# Display_Schematic.net
KiCad netlist of a schematic drawn in Altium Designer
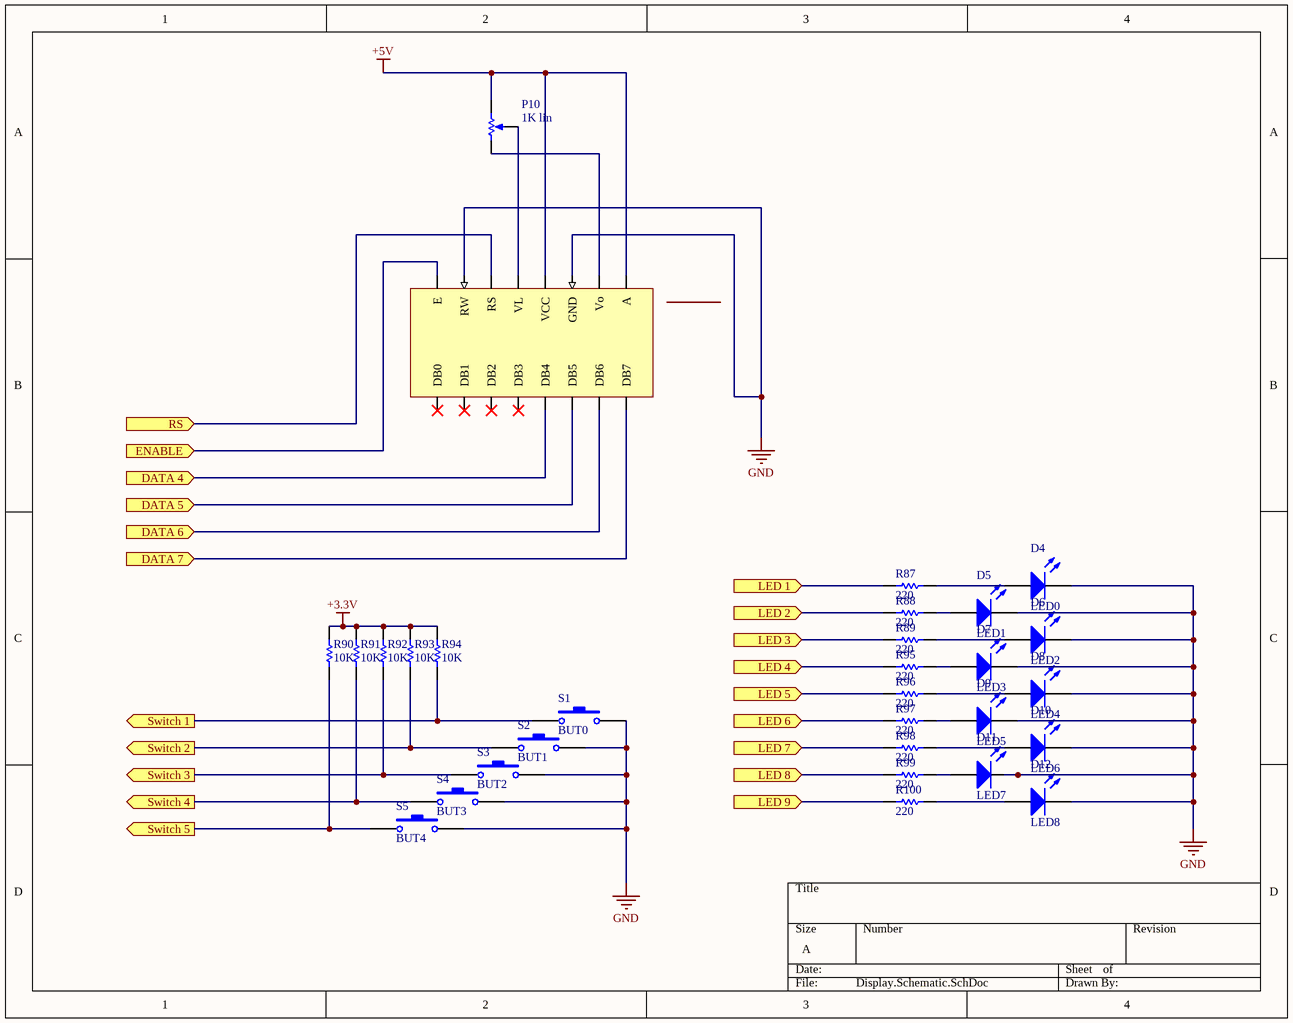
[diagram p0: Display.Schematic.SchDoc]

(export (version "E")
  (design (tool "Eeschema 10.0.6"))
  (components
    (comp (ref "D4")
      (value "LED0")
      (footprint "LED")
      (description "Typical INFRARED GaAs LED")
      (fields (field (name "PUBLISHER") "Altium Limited"))
      (libsource (lib "Miscellaneous Devices") (part "LED0"))
    )
    (comp (ref "D5")
      (value "LED1")
      (footprint "LED")
      (description "Typical INFRARED GaAs LED")
      (fields (field (name "PUBLISHER") "Altium Limited"))
      (libsource (lib "Miscellaneous Devices") (part "LED0"))
    )
    (comp (ref "D6")
      (value "LED2")
      (footprint "LED")
      (description "Typical INFRARED GaAs LED")
      (fields (field (name "PUBLISHER") "Altium Limited"))
      (libsource (lib "Miscellaneous Devices") (part "LED0"))
    )
    (comp (ref "D7")
      (value "LED3")
      (footprint "LED")
      (description "Typical INFRARED GaAs LED")
      (fields (field (name "PUBLISHER") "Altium Limited"))
      (libsource (lib "Miscellaneous Devices") (part "LED0"))
    )
    (comp (ref "D8")
      (value "LED4")
      (footprint "LED")
      (description "Typical INFRARED GaAs LED")
      (fields (field (name "PUBLISHER") "Altium Limited"))
      (libsource (lib "Miscellaneous Devices") (part "LED0"))
    )
    (comp (ref "D9")
      (value "LED5")
      (footprint "LED")
      (description "Typical INFRARED GaAs LED")
      (fields (field (name "PUBLISHER") "Altium Limited"))
      (libsource (lib "Miscellaneous Devices") (part "LED0"))
    )
    (comp (ref "D10")
      (value "LED6")
      (footprint "LED")
      (description "Typical INFRARED GaAs LED")
      (fields (field (name "PUBLISHER") "Altium Limited"))
      (libsource (lib "Miscellaneous Devices") (part "LED0"))
    )
    (comp (ref "D11")
      (value "LED7")
      (footprint "LED")
      (description "Typical INFRARED GaAs LED")
      (fields (field (name "PUBLISHER") "Altium Limited"))
      (libsource (lib "Miscellaneous Devices") (part "LED0"))
    )
    (comp (ref "D12")
      (value "LED8")
      (footprint "LED")
      (description "Typical INFRARED GaAs LED")
      (fields (field (name "PUBLISHER") "Altium Limited"))
      (libsource (lib "Miscellaneous Devices") (part "LED0"))
    )
    (comp (ref "Display1")
      (value "16x2 LCD")
      (footprint "Display")
      (libsource (lib "display") (part "Display"))
    )
    (comp (ref "P10")
      (value "1K lin")
      (footprint "BOURNS Trim pot")
      (description "Potentiometer")
      (fields (field (name "PUBLISHER") "Altium Limited"))
      (libsource (lib "Miscellaneous Devices") (part "RPot"))
    )
    (comp (ref "R87")
      (value "220")
      (footprint "CAPC1608N")
      (description "Resistor")
      (fields (field (name "PUBLISHER") "Altium Limited"))
      (libsource (lib "Miscellaneous Devices") (part "Res1"))
    )
    (comp (ref "R88")
      (value "220")
      (footprint "CAPC1608N")
      (description "Resistor")
      (fields (field (name "PUBLISHER") "Altium Limited"))
      (libsource (lib "Miscellaneous Devices") (part "Res1"))
    )
    (comp (ref "R89")
      (value "220")
      (footprint "CAPC1608N")
      (description "Resistor")
      (fields (field (name "PUBLISHER") "Altium Limited"))
      (libsource (lib "Miscellaneous Devices") (part "Res1"))
    )
    (comp (ref "R90")
      (value "10K")
      (footprint "CAPC1608N")
      (description "Resistor")
      (fields (field (name "PUBLISHER") "Altium Limited"))
      (libsource (lib "Miscellaneous Devices") (part "Res1"))
    )
    (comp (ref "R91")
      (value "10K")
      (footprint "CAPC1608N")
      (description "Resistor")
      (fields (field (name "PUBLISHER") "Altium Limited"))
      (libsource (lib "Miscellaneous Devices") (part "Res1"))
    )
    (comp (ref "R92")
      (value "10K")
      (footprint "CAPC1608N")
      (description "Resistor")
      (fields (field (name "PUBLISHER") "Altium Limited"))
      (libsource (lib "Miscellaneous Devices") (part "Res1"))
    )
    (comp (ref "R93")
      (value "10K")
      (footprint "CAPC1608N")
      (description "Resistor")
      (fields (field (name "PUBLISHER") "Altium Limited"))
      (libsource (lib "Miscellaneous Devices") (part "Res1"))
    )
    (comp (ref "R94")
      (value "10K")
      (footprint "CAPC1608N")
      (description "Resistor")
      (fields (field (name "PUBLISHER") "Altium Limited"))
      (libsource (lib "Miscellaneous Devices") (part "Res1"))
    )
    (comp (ref "R95")
      (value "220")
      (footprint "CAPC1608N")
      (description "Resistor")
      (fields (field (name "PUBLISHER") "Altium Limited"))
      (libsource (lib "Miscellaneous Devices") (part "Res1"))
    )
    (comp (ref "R96")
      (value "220")
      (footprint "CAPC1608N")
      (description "Resistor")
      (fields (field (name "PUBLISHER") "Altium Limited"))
      (libsource (lib "Miscellaneous Devices") (part "Res1"))
    )
    (comp (ref "R97")
      (value "220")
      (footprint "CAPC1608N")
      (description "Resistor")
      (fields (field (name "PUBLISHER") "Altium Limited"))
      (libsource (lib "Miscellaneous Devices") (part "Res1"))
    )
    (comp (ref "R98")
      (value "220")
      (footprint "CAPC1608N")
      (description "Resistor")
      (fields (field (name "PUBLISHER") "Altium Limited"))
      (libsource (lib "Miscellaneous Devices") (part "Res1"))
    )
    (comp (ref "R99")
      (value "220")
      (footprint "CAPC1608N")
      (description "Resistor")
      (fields (field (name "PUBLISHER") "Altium Limited"))
      (libsource (lib "Miscellaneous Devices") (part "Res1"))
    )
    (comp (ref "R100")
      (value "220")
      (footprint "CAPC1608N")
      (description "Resistor")
      (fields (field (name "PUBLISHER") "Altium Limited"))
      (libsource (lib "Miscellaneous Devices") (part "Res1"))
    )
    (comp (ref "S1")
      (value "BUT0")
      (footprint "PUSH BUTTON")
      (description "Switch")
      (fields (field (name "PUBLISHER") "Altium Limited"))
      (libsource (lib "Miscellaneous Devices") (part "SW-PB"))
    )
    (comp (ref "S2")
      (value "BUT1")
      (footprint "PUSH BUTTON")
      (description "Switch")
      (fields (field (name "PUBLISHER") "Altium Limited"))
      (libsource (lib "Miscellaneous Devices") (part "SW-PB"))
    )
    (comp (ref "S3")
      (value "BUT2")
      (footprint "PUSH BUTTON")
      (description "Switch")
      (fields (field (name "PUBLISHER") "Altium Limited"))
      (libsource (lib "Miscellaneous Devices") (part "SW-PB"))
    )
    (comp (ref "S4")
      (value "BUT3")
      (footprint "PUSH BUTTON")
      (description "Switch")
      (fields (field (name "PUBLISHER") "Altium Limited"))
      (libsource (lib "Miscellaneous Devices") (part "SW-PB"))
    )
    (comp (ref "S5")
      (value "BUT4")
      (footprint "PUSH BUTTON")
      (description "Switch")
      (fields (field (name "PUBLISHER") "Altium Limited"))
      (libsource (lib "Miscellaneous Devices") (part "SW-PB"))
    )
  )
  (nets
    (net (code "1") (name "+3.3V") (class "Default")
      (node (ref "R90") (pin "2") (pinfunction "2_2") (pintype "passive"))
      (node (ref "R91") (pin "2") (pinfunction "2_2") (pintype "passive"))
      (node (ref "R92") (pin "2") (pinfunction "2_2") (pintype "passive"))
      (node (ref "R93") (pin "2") (pinfunction "2_2") (pintype "passive"))
      (node (ref "R94") (pin "2") (pinfunction "2_2") (pintype "passive"))
    )
    (net (code "2") (name "+5V") (class "Default")
      (node (ref "Display1") (pin "16") (pinfunction "A_16") (pintype "passive"))
      (node (ref "Display1") (pin "2") (pinfunction "VCC_2") (pintype "passive"))
      (node (ref "P10") (pin "2") (pinfunction "BOT_2") (pintype "passive"))
    )
    (net (code "3") (name "/DATA 4") (class "Default")
      (node (ref "Display1") (pin "10") (pinfunction "DB4_10") (pintype "passive"))
    )
    (net (code "4") (name "/DATA 5") (class "Default")
      (node (ref "Display1") (pin "9") (pinfunction "DB5_9") (pintype "passive"))
    )
    (net (code "5") (name "/DATA 6") (class "Default")
      (node (ref "Display1") (pin "8") (pinfunction "DB6_8") (pintype "passive"))
    )
    (net (code "6") (name "/DATA 7") (class "Default")
      (node (ref "Display1") (pin "7") (pinfunction "DB7_7") (pintype "passive"))
    )
    (net (code "7") (name "/ENABLE") (class "Default")
      (node (ref "Display1") (pin "6") (pinfunction "E_6") (pintype "passive"))
    )
    (net (code "8") (name "/LED 1") (class "Default")
      (node (ref "R87") (pin "1") (pinfunction "1_1") (pintype "passive"))
    )
    (net (code "9") (name "/LED 2") (class "Default")
      (node (ref "R88") (pin "1") (pinfunction "1_1") (pintype "passive"))
    )
    (net (code "10") (name "/LED 3") (class "Default")
      (node (ref "R89") (pin "1") (pinfunction "1_1") (pintype "passive"))
    )
    (net (code "11") (name "/LED 4") (class "Default")
      (node (ref "R95") (pin "1") (pinfunction "1_1") (pintype "passive"))
    )
    (net (code "12") (name "/LED 5") (class "Default")
      (node (ref "R96") (pin "1") (pinfunction "1_1") (pintype "passive"))
    )
    (net (code "13") (name "/LED 6") (class "Default")
      (node (ref "R97") (pin "1") (pinfunction "1_1") (pintype "passive"))
    )
    (net (code "14") (name "/LED 7") (class "Default")
      (node (ref "R98") (pin "1") (pinfunction "1_1") (pintype "passive"))
    )
    (net (code "15") (name "/LED 8") (class "Default")
      (node (ref "R99") (pin "1") (pinfunction "1_1") (pintype "passive"))
    )
    (net (code "16") (name "/LED 9") (class "Default")
      (node (ref "R100") (pin "1") (pinfunction "1_1") (pintype "passive"))
    )
    (net (code "17") (name "/RS") (class "Default")
      (node (ref "Display1") (pin "4") (pinfunction "RS_4") (pintype "passive"))
    )
    (net (code "18") (name "/Switch 1") (class "Default")
      (node (ref "R94") (pin "1") (pinfunction "1_1") (pintype "passive"))
      (node (ref "S1") (pin "1") (pinfunction "1_1") (pintype "passive"))
    )
    (net (code "19") (name "/Switch 2") (class "Default")
      (node (ref "R93") (pin "1") (pinfunction "1_1") (pintype "passive"))
      (node (ref "S2") (pin "1") (pinfunction "1_1") (pintype "passive"))
    )
    (net (code "20") (name "/Switch 3") (class "Default")
      (node (ref "R92") (pin "1") (pinfunction "1_1") (pintype "passive"))
      (node (ref "S3") (pin "1") (pinfunction "1_1") (pintype "passive"))
    )
    (net (code "21") (name "/Switch 4") (class "Default")
      (node (ref "R91") (pin "1") (pinfunction "1_1") (pintype "passive"))
      (node (ref "S4") (pin "1") (pinfunction "1_1") (pintype "passive"))
    )
    (net (code "22") (name "/Switch 5") (class "Default")
      (node (ref "R90") (pin "1") (pinfunction "1_1") (pintype "passive"))
      (node (ref "S5") (pin "1") (pinfunction "1_1") (pintype "passive"))
    )
    (net (code "23") (name "GND") (class "Default")
      (node (ref "D10") (pin "2") (pinfunction "K_2") (pintype "passive"))
      (node (ref "D11") (pin "2") (pinfunction "K_2") (pintype "passive"))
      (node (ref "D12") (pin "2") (pinfunction "K_2") (pintype "passive"))
      (node (ref "D4") (pin "2") (pinfunction "K_2") (pintype "passive"))
      (node (ref "D5") (pin "2") (pinfunction "K_2") (pintype "passive"))
      (node (ref "D6") (pin "2") (pinfunction "K_2") (pintype "passive"))
      (node (ref "D7") (pin "2") (pinfunction "K_2") (pintype "passive"))
      (node (ref "D8") (pin "2") (pinfunction "K_2") (pintype "passive"))
      (node (ref "D9") (pin "2") (pinfunction "K_2") (pintype "passive"))
      (node (ref "Display1") (pin "1") (pinfunction "GND_1") (pintype "input"))
      (node (ref "Display1") (pin "5") (pinfunction "RW_5") (pintype "input"))
      (node (ref "S1") (pin "2") (pinfunction "2_2") (pintype "passive"))
      (node (ref "S2") (pin "2") (pinfunction "2_2") (pintype "passive"))
      (node (ref "S3") (pin "2") (pinfunction "2_2") (pintype "passive"))
      (node (ref "S4") (pin "2") (pinfunction "2_2") (pintype "passive"))
      (node (ref "S5") (pin "2") (pinfunction "2_2") (pintype "passive"))
    )
    (net (code "24") (name "Net-(D4-A)") (class "Default")
      (node (ref "D4") (pin "1") (pinfunction "A_1") (pintype "passive"))
      (node (ref "R87") (pin "2") (pinfunction "2_2") (pintype "passive"))
    )
    (net (code "25") (name "Net-(D5-A)") (class "Default")
      (node (ref "D5") (pin "1") (pinfunction "A_1") (pintype "passive"))
      (node (ref "R88") (pin "2") (pinfunction "2_2") (pintype "passive"))
    )
    (net (code "26") (name "Net-(D6-A)") (class "Default")
      (node (ref "D6") (pin "1") (pinfunction "A_1") (pintype "passive"))
      (node (ref "R89") (pin "2") (pinfunction "2_2") (pintype "passive"))
    )
    (net (code "27") (name "Net-(D7-A)") (class "Default")
      (node (ref "D7") (pin "1") (pinfunction "A_1") (pintype "passive"))
      (node (ref "R95") (pin "2") (pinfunction "2_2") (pintype "passive"))
    )
    (net (code "28") (name "Net-(D8-A)") (class "Default")
      (node (ref "D8") (pin "1") (pinfunction "A_1") (pintype "passive"))
      (node (ref "R96") (pin "2") (pinfunction "2_2") (pintype "passive"))
    )
    (net (code "29") (name "Net-(D9-A)") (class "Default")
      (node (ref "D9") (pin "1") (pinfunction "A_1") (pintype "passive"))
      (node (ref "R97") (pin "2") (pinfunction "2_2") (pintype "passive"))
    )
    (net (code "30") (name "Net-(D10-A)") (class "Default")
      (node (ref "D10") (pin "1") (pinfunction "A_1") (pintype "passive"))
      (node (ref "R98") (pin "2") (pinfunction "2_2") (pintype "passive"))
    )
    (net (code "31") (name "Net-(D11-A)") (class "Default")
      (node (ref "D11") (pin "1") (pinfunction "A_1") (pintype "passive"))
      (node (ref "R99") (pin "2") (pinfunction "2_2") (pintype "passive"))
    )
    (net (code "32") (name "Net-(D12-A)") (class "Default")
      (node (ref "D12") (pin "1") (pinfunction "A_1") (pintype "passive"))
      (node (ref "R100") (pin "2") (pinfunction "2_2") (pintype "passive"))
    )
    (net (code "33") (name "Net-(Display1-VL)") (class "Default")
      (node (ref "Display1") (pin "3") (pinfunction "VL_3") (pintype "passive"))
      (node (ref "P10") (pin "3") (pinfunction "TAP_3") (pintype "passive"))
    )
    (net (code "34") (name "Net-(Display1-Vo)") (class "Default")
      (node (ref "Display1") (pin "15") (pinfunction "Vo_15") (pintype "passive"))
      (node (ref "P10") (pin "1") (pinfunction "TOP_1") (pintype "passive"))
    )
    (net (code "35") (name "unconnected-(Display1-DB0-Pad14)") (class "Default")
      (node (ref "Display1") (pin "14") (pinfunction "DB0_14") (pintype "passive+no_connect"))
    )
    (net (code "36") (name "unconnected-(Display1-DB1-Pad13)") (class "Default")
      (node (ref "Display1") (pin "13") (pinfunction "DB1_13") (pintype "passive+no_connect"))
    )
    (net (code "37") (name "unconnected-(Display1-DB2-Pad12)") (class "Default")
      (node (ref "Display1") (pin "12") (pinfunction "DB2_12") (pintype "passive+no_connect"))
    )
    (net (code "38") (name "unconnected-(Display1-DB3-Pad11)") (class "Default")
      (node (ref "Display1") (pin "11") (pinfunction "DB3_11") (pintype "passive+no_connect"))
    )
  )
)
